# 07_EL_CON.net
KiCad netlist of a schematic drawn in Altium Designer
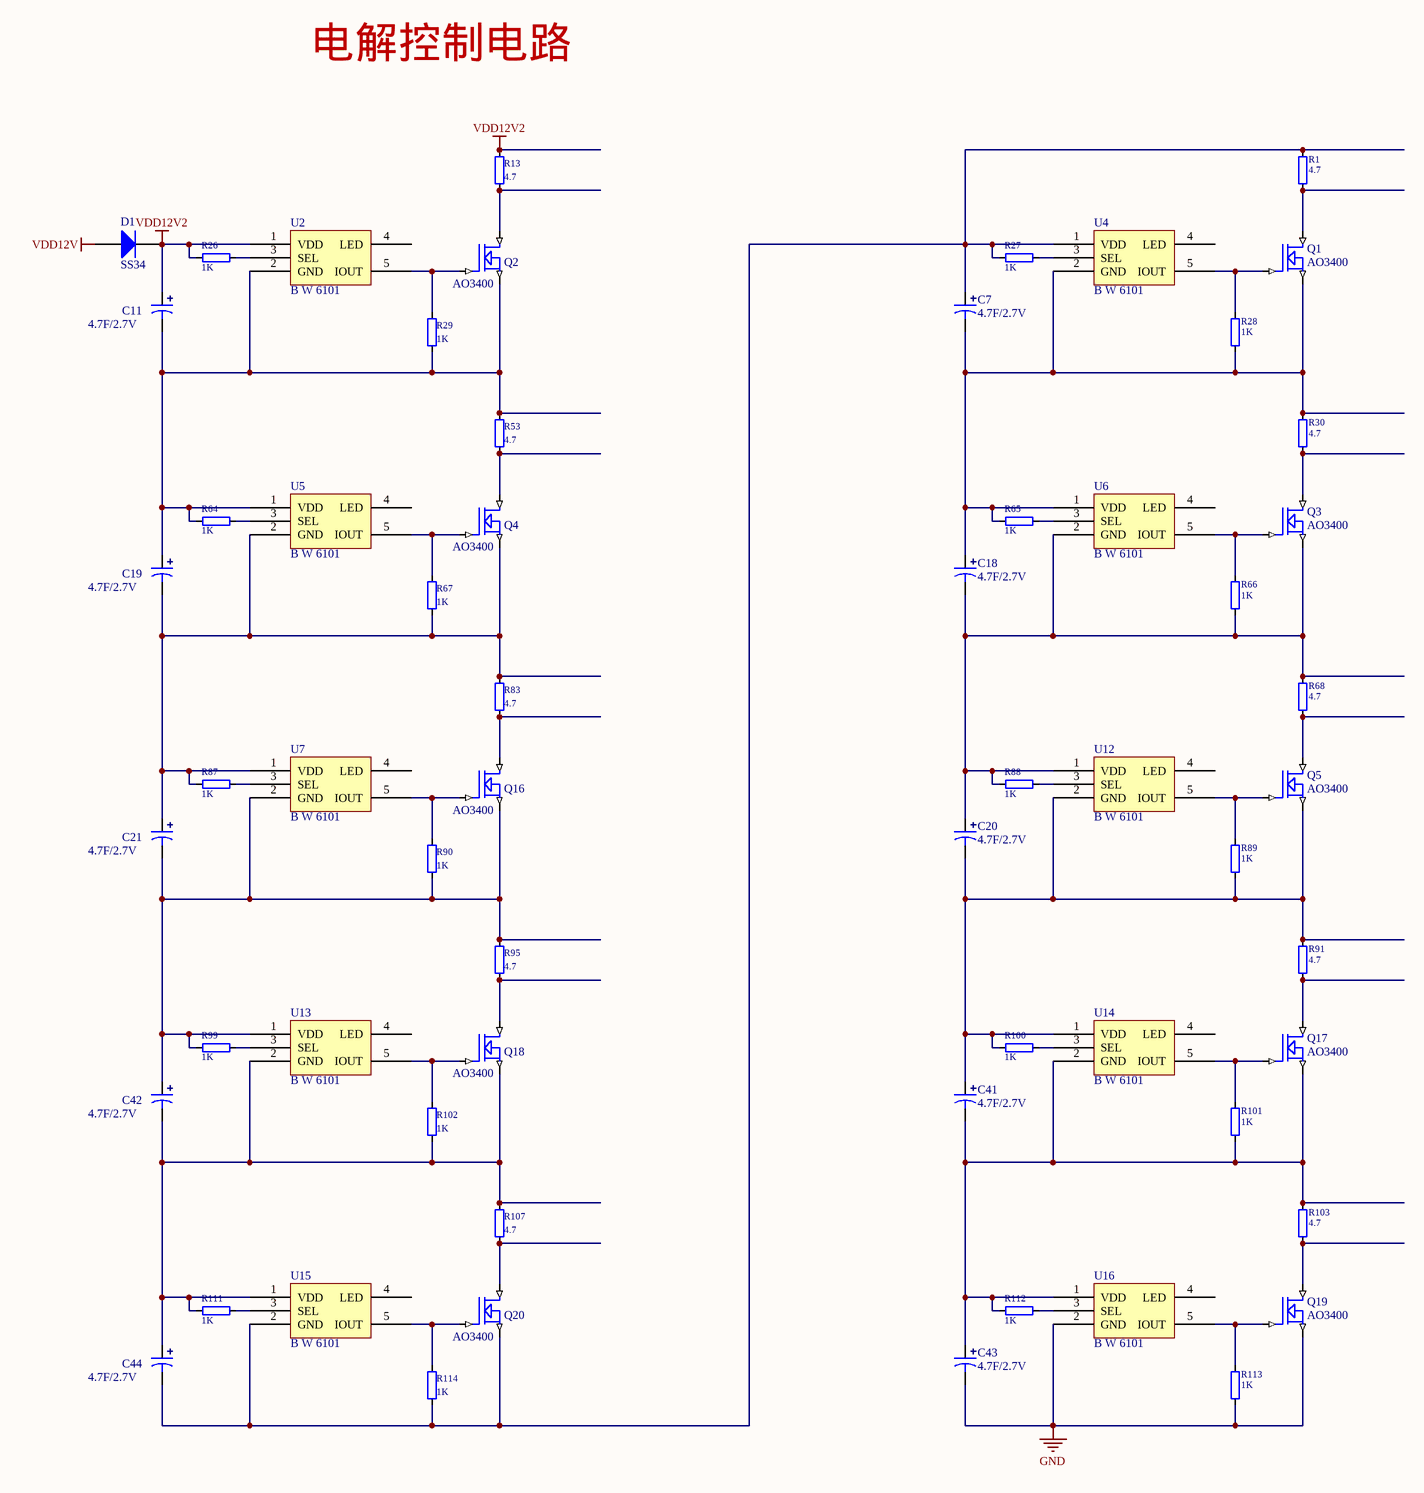
[diagram p0: 07_EL_CON.SchDoc]

(export (version "E")
  (design (tool "Eeschema 10.0.6"))
  (components
    (comp (ref "C7")
      (value "4.7F/2.7V")
      (footprint "10*16 -5")
      (description "电解电容")
      (libsource (lib "XiaoyI") (part "CAP2"))
    )
    (comp (ref "C11")
      (value "4.7F/2.7V")
      (footprint "10*16 -5")
      (description "电解电容")
      (libsource (lib "XiaoyI") (part "CAP2"))
    )
    (comp (ref "C18")
      (value "4.7F/2.7V")
      (footprint "10*16 -5")
      (description "电解电容")
      (libsource (lib "XiaoyI") (part "CAP2"))
    )
    (comp (ref "C19")
      (value "4.7F/2.7V")
      (footprint "10*16 -5")
      (description "电解电容")
      (libsource (lib "XiaoyI") (part "CAP2"))
    )
    (comp (ref "C20")
      (value "4.7F/2.7V")
      (footprint "10*16 -5")
      (description "电解电容")
      (libsource (lib "XiaoyI") (part "CAP2"))
    )
    (comp (ref "C21")
      (value "4.7F/2.7V")
      (footprint "10*16 -5")
      (description "电解电容")
      (libsource (lib "XiaoyI") (part "CAP2"))
    )
    (comp (ref "C41")
      (value "4.7F/2.7V")
      (footprint "10*16 -5")
      (description "电解电容")
      (libsource (lib "XiaoyI") (part "CAP2"))
    )
    (comp (ref "C42")
      (value "4.7F/2.7V")
      (footprint "10*16 -5")
      (description "电解电容")
      (libsource (lib "XiaoyI") (part "CAP2"))
    )
    (comp (ref "C43")
      (value "4.7F/2.7V")
      (footprint "10*16 -5")
      (description "电解电容")
      (libsource (lib "XiaoyI") (part "CAP2"))
    )
    (comp (ref "C44")
      (value "4.7F/2.7V")
      (footprint "10*16 -5")
      (description "电解电容")
      (libsource (lib "XiaoyI") (part "CAP2"))
    )
    (comp (ref "D1") (value "SS34") (footprint "SMA") (libsource (lib "Sch_library") (part "DIODE")))
    (comp (ref "Q1")
      (value "AO3400")
      (footprint "SOT-23")
      (description "MOSFET N")
      (libsource (lib "XiaoyI") (part "MOSFET N"))
    )
    (comp (ref "Q2")
      (value "AO3400")
      (footprint "SOT-23")
      (description "MOSFET N")
      (libsource (lib "XiaoyI") (part "MOSFET N"))
    )
    (comp (ref "Q3")
      (value "AO3400")
      (footprint "SOT-23")
      (description "MOSFET N")
      (libsource (lib "XiaoyI") (part "MOSFET N"))
    )
    (comp (ref "Q4")
      (value "AO3400")
      (footprint "SOT-23")
      (description "MOSFET N")
      (libsource (lib "XiaoyI") (part "MOSFET N"))
    )
    (comp (ref "Q5")
      (value "AO3400")
      (footprint "SOT-23")
      (description "MOSFET N")
      (libsource (lib "XiaoyI") (part "MOSFET N"))
    )
    (comp (ref "Q16")
      (value "AO3400")
      (footprint "SOT-23")
      (description "MOSFET N")
      (libsource (lib "XiaoyI") (part "MOSFET N"))
    )
    (comp (ref "Q17")
      (value "AO3400")
      (footprint "SOT-23")
      (description "MOSFET N")
      (libsource (lib "XiaoyI") (part "MOSFET N"))
    )
    (comp (ref "Q18")
      (value "AO3400")
      (footprint "SOT-23")
      (description "MOSFET N")
      (libsource (lib "XiaoyI") (part "MOSFET N"))
    )
    (comp (ref "Q19")
      (value "AO3400")
      (footprint "SOT-23")
      (description "MOSFET N")
      (libsource (lib "XiaoyI") (part "MOSFET N"))
    )
    (comp (ref "Q20")
      (value "AO3400")
      (footprint "SOT-23")
      (description "MOSFET N")
      (libsource (lib "XiaoyI") (part "MOSFET N"))
    )
    (comp (ref "R1") (value "4.7") (footprint "2010R") (libsource (lib "*") (part "RES")))
    (comp (ref "R13") (value "4.7") (footprint "2010R") (libsource (lib "*") (part "RES")))
    (comp (ref "R26") (value "1K") (footprint "0603R") (libsource (lib "*") (part "RES")))
    (comp (ref "R27") (value "1K") (footprint "0603R") (libsource (lib "*") (part "RES")))
    (comp (ref "R28") (value "1K") (footprint "0603R") (libsource (lib "*") (part "RES")))
    (comp (ref "R29") (value "1K") (footprint "0603R") (libsource (lib "*") (part "RES")))
    (comp (ref "R30") (value "4.7") (footprint "2010R") (libsource (lib "*") (part "RES")))
    (comp (ref "R53") (value "4.7") (footprint "2010R") (libsource (lib "*") (part "RES")))
    (comp (ref "R64") (value "1K") (footprint "0603R") (libsource (lib "*") (part "RES")))
    (comp (ref "R65") (value "1K") (footprint "0603R") (libsource (lib "*") (part "RES")))
    (comp (ref "R66") (value "1K") (footprint "0603R") (libsource (lib "*") (part "RES")))
    (comp (ref "R67") (value "1K") (footprint "0603R") (libsource (lib "*") (part "RES")))
    (comp (ref "R68") (value "4.7") (footprint "2010R") (libsource (lib "*") (part "RES")))
    (comp (ref "R83") (value "4.7") (footprint "2010R") (libsource (lib "*") (part "RES")))
    (comp (ref "R87") (value "1K") (footprint "0603R") (libsource (lib "*") (part "RES")))
    (comp (ref "R88") (value "1K") (footprint "0603R") (libsource (lib "*") (part "RES")))
    (comp (ref "R89") (value "1K") (footprint "0603R") (libsource (lib "*") (part "RES")))
    (comp (ref "R90") (value "1K") (footprint "0603R") (libsource (lib "*") (part "RES")))
    (comp (ref "R91") (value "4.7") (footprint "2010R") (libsource (lib "*") (part "RES")))
    (comp (ref "R95") (value "4.7") (footprint "2010R") (libsource (lib "*") (part "RES")))
    (comp (ref "R99") (value "1K") (footprint "0603R") (libsource (lib "*") (part "RES")))
    (comp (ref "R100") (value "1K") (footprint "0603R") (libsource (lib "*") (part "RES")))
    (comp (ref "R101") (value "1K") (footprint "0603R") (libsource (lib "*") (part "RES")))
    (comp (ref "R102") (value "1K") (footprint "0603R") (libsource (lib "*") (part "RES")))
    (comp (ref "R103") (value "4.7") (footprint "2010R") (libsource (lib "*") (part "RES")))
    (comp (ref "R107") (value "4.7") (footprint "2010R") (libsource (lib "*") (part "RES")))
    (comp (ref "R111") (value "1K") (footprint "0603R") (libsource (lib "*") (part "RES")))
    (comp (ref "R112") (value "1K") (footprint "0603R") (libsource (lib "*") (part "RES")))
    (comp (ref "R113") (value "1K") (footprint "0603R") (libsource (lib "*") (part "RES")))
    (comp (ref "R114") (value "1K") (footprint "0603R") (libsource (lib "*") (part "RES")))
    (comp (ref "U2") (value "B W 6101") (footprint "SOT23-5") (libsource (lib "stm32") (part "B W 6101")))
    (comp (ref "U4") (value "B W 6101") (footprint "SOT23-5") (libsource (lib "stm32") (part "B W 6101")))
    (comp (ref "U5") (value "B W 6101") (footprint "SOT23-5") (libsource (lib "stm32") (part "B W 6101")))
    (comp (ref "U6") (value "B W 6101") (footprint "SOT23-5") (libsource (lib "stm32") (part "B W 6101")))
    (comp (ref "U7") (value "B W 6101") (footprint "SOT23-5") (libsource (lib "stm32") (part "B W 6101")))
    (comp (ref "U12") (value "B W 6101") (footprint "SOT23-5") (libsource (lib "stm32") (part "B W 6101")))
    (comp (ref "U13") (value "B W 6101") (footprint "SOT23-5") (libsource (lib "stm32") (part "B W 6101")))
    (comp (ref "U14") (value "B W 6101") (footprint "SOT23-5") (libsource (lib "stm32") (part "B W 6101")))
    (comp (ref "U15") (value "B W 6101") (footprint "SOT23-5") (libsource (lib "stm32") (part "B W 6101")))
    (comp (ref "U16") (value "B W 6101") (footprint "SOT23-5") (libsource (lib "stm32") (part "B W 6101")))
  )
  (nets
    (net (code "1") (name "GND") (class "Default")
      (node (ref "C43") (pin "2") (pinfunction "2_2") (pintype "passive"))
      (node (ref "Q19") (pin "2") (pinfunction "S_2") (pintype "output"))
      (node (ref "R113") (pin "2") (pinfunction "2_2") (pintype "passive"))
      (node (ref "U16") (pin "2") (pinfunction "GND_2") (pintype "passive"))
    )
    (net (code "2") (name "Net-(Q1-D)") (class "Default")
      (node (ref "Q1") (pin "3") (pinfunction "D_3") (pintype "input"))
      (node (ref "R1") (pin "2") (pinfunction "2_2") (pintype "passive"))
    )
    (net (code "3") (name "Net-(Q1-G)") (class "Default")
      (node (ref "Q1") (pin "1") (pinfunction "G_1") (pintype "input"))
      (node (ref "R28") (pin "1") (pinfunction "1_1") (pintype "passive"))
      (node (ref "U4") (pin "5") (pinfunction "IOUT_5") (pintype "passive"))
    )
    (net (code "4") (name "Net-(Q1-S)") (class "Default")
      (node (ref "C18") (pin "1") (pinfunction "1_1") (pintype "passive"))
      (node (ref "C7") (pin "2") (pinfunction "2_2") (pintype "passive"))
      (node (ref "Q1") (pin "2") (pinfunction "S_2") (pintype "output"))
      (node (ref "R28") (pin "2") (pinfunction "2_2") (pintype "passive"))
      (node (ref "R30") (pin "1") (pinfunction "1_1") (pintype "passive"))
      (node (ref "R65") (pin "1") (pinfunction "1_1") (pintype "passive"))
      (node (ref "U4") (pin "2") (pinfunction "GND_2") (pintype "passive"))
      (node (ref "U6") (pin "1") (pinfunction "VDD_1") (pintype "passive"))
    )
    (net (code "5") (name "Net-(Q2-D)") (class "Default")
      (node (ref "Q2") (pin "3") (pinfunction "D_3") (pintype "input"))
      (node (ref "R13") (pin "2") (pinfunction "2_2") (pintype "passive"))
    )
    (net (code "6") (name "Net-(Q2-G)") (class "Default")
      (node (ref "Q2") (pin "1") (pinfunction "G_1") (pintype "input"))
      (node (ref "R29") (pin "1") (pinfunction "1_1") (pintype "passive"))
      (node (ref "U2") (pin "5") (pinfunction "IOUT_5") (pintype "passive"))
    )
    (net (code "7") (name "Net-(Q2-S)") (class "Default")
      (node (ref "C11") (pin "2") (pinfunction "2_2") (pintype "passive"))
      (node (ref "C19") (pin "1") (pinfunction "1_1") (pintype "passive"))
      (node (ref "Q2") (pin "2") (pinfunction "S_2") (pintype "output"))
      (node (ref "R29") (pin "2") (pinfunction "2_2") (pintype "passive"))
      (node (ref "R53") (pin "1") (pinfunction "1_1") (pintype "passive"))
      (node (ref "R64") (pin "1") (pinfunction "1_1") (pintype "passive"))
      (node (ref "U2") (pin "2") (pinfunction "GND_2") (pintype "passive"))
      (node (ref "U5") (pin "1") (pinfunction "VDD_1") (pintype "passive"))
    )
    (net (code "8") (name "Net-(Q3-D)") (class "Default")
      (node (ref "Q3") (pin "3") (pinfunction "D_3") (pintype "input"))
      (node (ref "R30") (pin "2") (pinfunction "2_2") (pintype "passive"))
    )
    (net (code "9") (name "Net-(Q3-G)") (class "Default")
      (node (ref "Q3") (pin "1") (pinfunction "G_1") (pintype "input"))
      (node (ref "R66") (pin "1") (pinfunction "1_1") (pintype "passive"))
      (node (ref "U6") (pin "5") (pinfunction "IOUT_5") (pintype "passive"))
    )
    (net (code "10") (name "Net-(Q3-S)") (class "Default")
      (node (ref "C18") (pin "2") (pinfunction "2_2") (pintype "passive"))
      (node (ref "C20") (pin "1") (pinfunction "1_1") (pintype "passive"))
      (node (ref "Q3") (pin "2") (pinfunction "S_2") (pintype "output"))
      (node (ref "R66") (pin "2") (pinfunction "2_2") (pintype "passive"))
      (node (ref "R68") (pin "1") (pinfunction "1_1") (pintype "passive"))
      (node (ref "R88") (pin "1") (pinfunction "1_1") (pintype "passive"))
      (node (ref "U12") (pin "1") (pinfunction "VDD_1") (pintype "passive"))
      (node (ref "U6") (pin "2") (pinfunction "GND_2") (pintype "passive"))
    )
    (net (code "11") (name "Net-(Q4-D)") (class "Default")
      (node (ref "Q4") (pin "3") (pinfunction "D_3") (pintype "input"))
      (node (ref "R53") (pin "2") (pinfunction "2_2") (pintype "passive"))
    )
    (net (code "12") (name "Net-(Q4-G)") (class "Default")
      (node (ref "Q4") (pin "1") (pinfunction "G_1") (pintype "input"))
      (node (ref "R67") (pin "1") (pinfunction "1_1") (pintype "passive"))
      (node (ref "U5") (pin "5") (pinfunction "IOUT_5") (pintype "passive"))
    )
    (net (code "13") (name "Net-(Q4-S)") (class "Default")
      (node (ref "C19") (pin "2") (pinfunction "2_2") (pintype "passive"))
      (node (ref "C21") (pin "1") (pinfunction "1_1") (pintype "passive"))
      (node (ref "Q4") (pin "2") (pinfunction "S_2") (pintype "output"))
      (node (ref "R67") (pin "2") (pinfunction "2_2") (pintype "passive"))
      (node (ref "R83") (pin "1") (pinfunction "1_1") (pintype "passive"))
      (node (ref "R87") (pin "1") (pinfunction "1_1") (pintype "passive"))
      (node (ref "U5") (pin "2") (pinfunction "GND_2") (pintype "passive"))
      (node (ref "U7") (pin "1") (pinfunction "VDD_1") (pintype "passive"))
    )
    (net (code "14") (name "Net-(Q5-D)") (class "Default")
      (node (ref "Q5") (pin "3") (pinfunction "D_3") (pintype "input"))
      (node (ref "R68") (pin "2") (pinfunction "2_2") (pintype "passive"))
    )
    (net (code "15") (name "Net-(Q5-G)") (class "Default")
      (node (ref "Q5") (pin "1") (pinfunction "G_1") (pintype "input"))
      (node (ref "R89") (pin "1") (pinfunction "1_1") (pintype "passive"))
      (node (ref "U12") (pin "5") (pinfunction "IOUT_5") (pintype "passive"))
    )
    (net (code "16") (name "Net-(Q5-S)") (class "Default")
      (node (ref "C20") (pin "2") (pinfunction "2_2") (pintype "passive"))
      (node (ref "C41") (pin "1") (pinfunction "1_1") (pintype "passive"))
      (node (ref "Q5") (pin "2") (pinfunction "S_2") (pintype "output"))
      (node (ref "R100") (pin "1") (pinfunction "1_1") (pintype "passive"))
      (node (ref "R89") (pin "2") (pinfunction "2_2") (pintype "passive"))
      (node (ref "R91") (pin "1") (pinfunction "1_1") (pintype "passive"))
      (node (ref "U12") (pin "2") (pinfunction "GND_2") (pintype "passive"))
      (node (ref "U14") (pin "1") (pinfunction "VDD_1") (pintype "passive"))
    )
    (net (code "17") (name "Net-(Q16-D)") (class "Default")
      (node (ref "Q16") (pin "3") (pinfunction "D_3") (pintype "input"))
      (node (ref "R83") (pin "2") (pinfunction "2_2") (pintype "passive"))
    )
    (net (code "18") (name "Net-(Q16-G)") (class "Default")
      (node (ref "Q16") (pin "1") (pinfunction "G_1") (pintype "input"))
      (node (ref "R90") (pin "1") (pinfunction "1_1") (pintype "passive"))
      (node (ref "U7") (pin "5") (pinfunction "IOUT_5") (pintype "passive"))
    )
    (net (code "19") (name "Net-(Q16-S)") (class "Default")
      (node (ref "C21") (pin "2") (pinfunction "2_2") (pintype "passive"))
      (node (ref "C42") (pin "1") (pinfunction "1_1") (pintype "passive"))
      (node (ref "Q16") (pin "2") (pinfunction "S_2") (pintype "output"))
      (node (ref "R90") (pin "2") (pinfunction "2_2") (pintype "passive"))
      (node (ref "R95") (pin "1") (pinfunction "1_1") (pintype "passive"))
      (node (ref "R99") (pin "1") (pinfunction "1_1") (pintype "passive"))
      (node (ref "U13") (pin "1") (pinfunction "VDD_1") (pintype "passive"))
      (node (ref "U7") (pin "2") (pinfunction "GND_2") (pintype "passive"))
    )
    (net (code "20") (name "Net-(Q17-D)") (class "Default")
      (node (ref "Q17") (pin "3") (pinfunction "D_3") (pintype "input"))
      (node (ref "R91") (pin "2") (pinfunction "2_2") (pintype "passive"))
    )
    (net (code "21") (name "Net-(Q17-G)") (class "Default")
      (node (ref "Q17") (pin "1") (pinfunction "G_1") (pintype "input"))
      (node (ref "R101") (pin "1") (pinfunction "1_1") (pintype "passive"))
      (node (ref "U14") (pin "5") (pinfunction "IOUT_5") (pintype "passive"))
    )
    (net (code "22") (name "Net-(Q17-S)") (class "Default")
      (node (ref "C41") (pin "2") (pinfunction "2_2") (pintype "passive"))
      (node (ref "C43") (pin "1") (pinfunction "1_1") (pintype "passive"))
      (node (ref "Q17") (pin "2") (pinfunction "S_2") (pintype "output"))
      (node (ref "R101") (pin "2") (pinfunction "2_2") (pintype "passive"))
      (node (ref "R103") (pin "1") (pinfunction "1_1") (pintype "passive"))
      (node (ref "R112") (pin "1") (pinfunction "1_1") (pintype "passive"))
      (node (ref "U14") (pin "2") (pinfunction "GND_2") (pintype "passive"))
      (node (ref "U16") (pin "1") (pinfunction "VDD_1") (pintype "passive"))
    )
    (net (code "23") (name "Net-(Q18-D)") (class "Default")
      (node (ref "Q18") (pin "3") (pinfunction "D_3") (pintype "input"))
      (node (ref "R95") (pin "2") (pinfunction "2_2") (pintype "passive"))
    )
    (net (code "24") (name "Net-(Q18-G)") (class "Default")
      (node (ref "Q18") (pin "1") (pinfunction "G_1") (pintype "input"))
      (node (ref "R102") (pin "1") (pinfunction "1_1") (pintype "passive"))
      (node (ref "U13") (pin "5") (pinfunction "IOUT_5") (pintype "passive"))
    )
    (net (code "25") (name "Net-(Q18-S)") (class "Default")
      (node (ref "C42") (pin "2") (pinfunction "2_2") (pintype "passive"))
      (node (ref "C44") (pin "1") (pinfunction "1_1") (pintype "passive"))
      (node (ref "Q18") (pin "2") (pinfunction "S_2") (pintype "output"))
      (node (ref "R102") (pin "2") (pinfunction "2_2") (pintype "passive"))
      (node (ref "R107") (pin "1") (pinfunction "1_1") (pintype "passive"))
      (node (ref "R111") (pin "1") (pinfunction "1_1") (pintype "passive"))
      (node (ref "U13") (pin "2") (pinfunction "GND_2") (pintype "passive"))
      (node (ref "U15") (pin "1") (pinfunction "VDD_1") (pintype "passive"))
    )
    (net (code "26") (name "Net-(Q19-D)") (class "Default")
      (node (ref "Q19") (pin "3") (pinfunction "D_3") (pintype "input"))
      (node (ref "R103") (pin "2") (pinfunction "2_2") (pintype "passive"))
    )
    (net (code "27") (name "Net-(Q19-G)") (class "Default")
      (node (ref "Q19") (pin "1") (pinfunction "G_1") (pintype "input"))
      (node (ref "R113") (pin "1") (pinfunction "1_1") (pintype "passive"))
      (node (ref "U16") (pin "5") (pinfunction "IOUT_5") (pintype "passive"))
    )
    (net (code "28") (name "Net-(Q20-D)") (class "Default")
      (node (ref "Q20") (pin "3") (pinfunction "D_3") (pintype "input"))
      (node (ref "R107") (pin "2") (pinfunction "2_2") (pintype "passive"))
    )
    (net (code "29") (name "Net-(Q20-G)") (class "Default")
      (node (ref "Q20") (pin "1") (pinfunction "G_1") (pintype "input"))
      (node (ref "R114") (pin "1") (pinfunction "1_1") (pintype "passive"))
      (node (ref "U15") (pin "5") (pinfunction "IOUT_5") (pintype "passive"))
    )
    (net (code "30") (name "Net-(Q20-S)") (class "Default")
      (node (ref "C44") (pin "2") (pinfunction "2_2") (pintype "passive"))
      (node (ref "C7") (pin "1") (pinfunction "1_1") (pintype "passive"))
      (node (ref "Q20") (pin "2") (pinfunction "S_2") (pintype "output"))
      (node (ref "R1") (pin "1") (pinfunction "1_1") (pintype "passive"))
      (node (ref "R114") (pin "2") (pinfunction "2_2") (pintype "passive"))
      (node (ref "R27") (pin "1") (pinfunction "1_1") (pintype "passive"))
      (node (ref "U15") (pin "2") (pinfunction "GND_2") (pintype "passive"))
      (node (ref "U4") (pin "1") (pinfunction "VDD_1") (pintype "passive"))
    )
    (net (code "31") (name "Net-(U2-SEL)") (class "Default")
      (node (ref "R26") (pin "2") (pinfunction "2_2") (pintype "passive"))
      (node (ref "U2") (pin "3") (pinfunction "SEL_3") (pintype "passive"))
    )
    (net (code "32") (name "Net-(U4-SEL)") (class "Default")
      (node (ref "R27") (pin "2") (pinfunction "2_2") (pintype "passive"))
      (node (ref "U4") (pin "3") (pinfunction "SEL_3") (pintype "passive"))
    )
    (net (code "33") (name "Net-(U5-SEL)") (class "Default")
      (node (ref "R64") (pin "2") (pinfunction "2_2") (pintype "passive"))
      (node (ref "U5") (pin "3") (pinfunction "SEL_3") (pintype "passive"))
    )
    (net (code "34") (name "Net-(U6-SEL)") (class "Default")
      (node (ref "R65") (pin "2") (pinfunction "2_2") (pintype "passive"))
      (node (ref "U6") (pin "3") (pinfunction "SEL_3") (pintype "passive"))
    )
    (net (code "35") (name "Net-(U7-SEL)") (class "Default")
      (node (ref "R87") (pin "2") (pinfunction "2_2") (pintype "passive"))
      (node (ref "U7") (pin "3") (pinfunction "SEL_3") (pintype "passive"))
    )
    (net (code "36") (name "Net-(U12-SEL)") (class "Default")
      (node (ref "R88") (pin "2") (pinfunction "2_2") (pintype "passive"))
      (node (ref "U12") (pin "3") (pinfunction "SEL_3") (pintype "passive"))
    )
    (net (code "37") (name "Net-(U13-SEL)") (class "Default")
      (node (ref "R99") (pin "2") (pinfunction "2_2") (pintype "passive"))
      (node (ref "U13") (pin "3") (pinfunction "SEL_3") (pintype "passive"))
    )
    (net (code "38") (name "Net-(U14-SEL)") (class "Default")
      (node (ref "R100") (pin "2") (pinfunction "2_2") (pintype "passive"))
      (node (ref "U14") (pin "3") (pinfunction "SEL_3") (pintype "passive"))
    )
    (net (code "39") (name "Net-(U15-SEL)") (class "Default")
      (node (ref "R111") (pin "2") (pinfunction "2_2") (pintype "passive"))
      (node (ref "U15") (pin "3") (pinfunction "SEL_3") (pintype "passive"))
    )
    (net (code "40") (name "Net-(U16-SEL)") (class "Default")
      (node (ref "R112") (pin "2") (pinfunction "2_2") (pintype "passive"))
      (node (ref "U16") (pin "3") (pinfunction "SEL_3") (pintype "passive"))
    )
    (net (code "41") (name "VDD12V") (class "Default")
      (node (ref "D1") (pin "1") (pinfunction "A_1") (pintype "passive"))
    )
    (net (code "42") (name "VDD12V2") (class "Default")
      (node (ref "C11") (pin "1") (pinfunction "1_1") (pintype "passive"))
      (node (ref "D1") (pin "2") (pinfunction "K_2") (pintype "passive"))
      (node (ref "R13") (pin "1") (pinfunction "1_1") (pintype "passive"))
      (node (ref "R26") (pin "1") (pinfunction "1_1") (pintype "passive"))
      (node (ref "U2") (pin "1") (pinfunction "VDD_1") (pintype "passive"))
    )
    (net (code "43") (name "unconnected-(U2-LED-Pad4)") (class "Default")
      (node (ref "U2") (pin "4") (pinfunction "LED_4") (pintype "passive"))
    )
    (net (code "44") (name "unconnected-(U4-LED-Pad4)") (class "Default")
      (node (ref "U4") (pin "4") (pinfunction "LED_4") (pintype "passive"))
    )
    (net (code "45") (name "unconnected-(U5-LED-Pad4)") (class "Default")
      (node (ref "U5") (pin "4") (pinfunction "LED_4") (pintype "passive"))
    )
    (net (code "46") (name "unconnected-(U6-LED-Pad4)") (class "Default")
      (node (ref "U6") (pin "4") (pinfunction "LED_4") (pintype "passive"))
    )
    (net (code "47") (name "unconnected-(U7-LED-Pad4)") (class "Default")
      (node (ref "U7") (pin "4") (pinfunction "LED_4") (pintype "passive"))
    )
    (net (code "48") (name "unconnected-(U12-LED-Pad4)") (class "Default")
      (node (ref "U12") (pin "4") (pinfunction "LED_4") (pintype "passive"))
    )
    (net (code "49") (name "unconnected-(U13-LED-Pad4)") (class "Default")
      (node (ref "U13") (pin "4") (pinfunction "LED_4") (pintype "passive"))
    )
    (net (code "50") (name "unconnected-(U14-LED-Pad4)") (class "Default")
      (node (ref "U14") (pin "4") (pinfunction "LED_4") (pintype "passive"))
    )
    (net (code "51") (name "unconnected-(U15-LED-Pad4)") (class "Default")
      (node (ref "U15") (pin "4") (pinfunction "LED_4") (pintype "passive"))
    )
    (net (code "52") (name "unconnected-(U16-LED-Pad4)") (class "Default")
      (node (ref "U16") (pin "4") (pinfunction "LED_4") (pintype "passive"))
    )
  )
)
